# general_Interface.net
KiCad netlist of a schematic drawn in Altium Designer
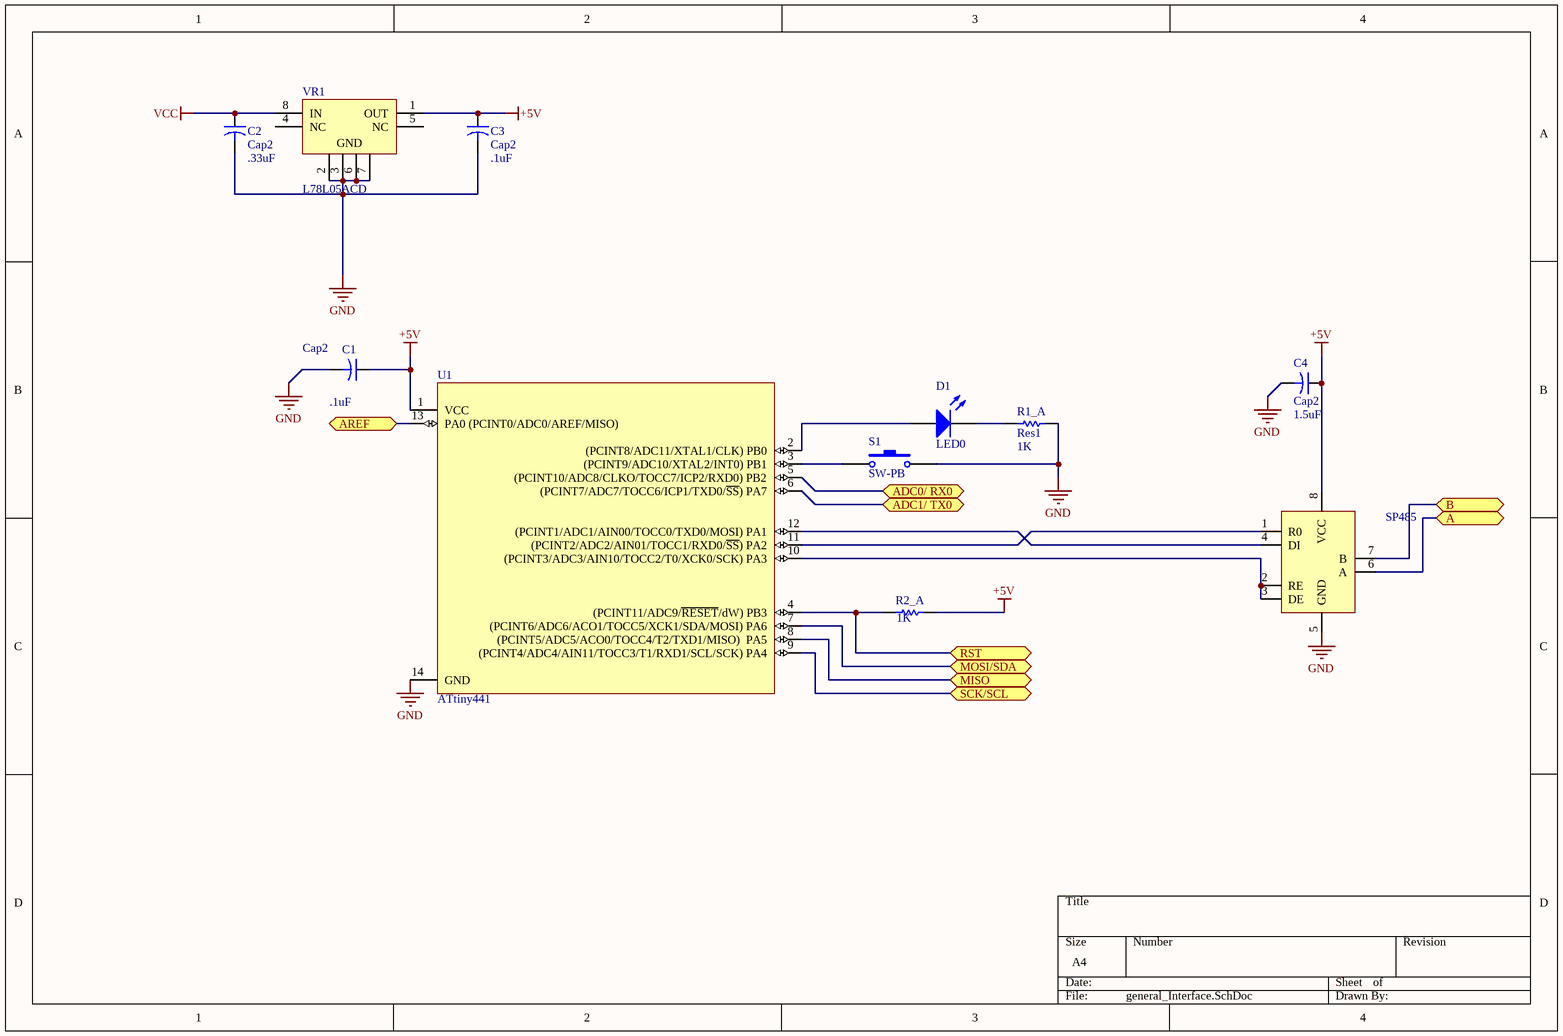
[diagram p0: general_Interface.SchDoc]

(export (version "E")
  (design (tool "Eeschema 10.0.6"))
  (components
    (comp (ref "C1")
      (value "Cap2")
      (footprint "6-0805_N")
      (description "Capacitor")
      (fields (field (name "ALTIUM_VALUE") ".1uF") (field (name "PUBLISHER") "Altium Limited"))
      (libsource (lib "Miscellaneous Devices") (part "Cap2"))
    )
    (comp (ref "C2")
      (value "Cap2")
      (footprint "6-0805_N")
      (description "Capacitor")
      (fields (field (name "ALTIUM_VALUE") ".33uF") (field (name "PUBLISHER") "Altium Limited"))
      (libsource (lib "Miscellaneous Devices") (part "Cap2"))
    )
    (comp (ref "C3")
      (value "Cap2")
      (footprint "6-0805_N")
      (description "Capacitor")
      (fields (field (name "ALTIUM_VALUE") ".1uF") (field (name "PUBLISHER") "Altium Limited"))
      (libsource (lib "Miscellaneous Devices") (part "Cap2"))
    )
    (comp (ref "C4")
      (value "Cap2")
      (footprint "6-0805_N")
      (description "Capacitor")
      (fields (field (name "ALTIUM_VALUE") "1.5uF") (field (name "PUBLISHER") "Altium Limited"))
      (libsource (lib "Miscellaneous Devices") (part "Cap2"))
    )
    (comp (ref "D1")
      (value "LED0")
      (footprint "1608[0603]")
      (description "Typical INFRARED GaAs LED")
      (fields (field (name "PUBLISHER") "Altium Limited"))
      (libsource (lib "Miscellaneous Devices") (part "LED0"))
    )
    (comp (ref "R1_A")
      (value "Res1")
      (footprint "6-0805_N")
      (description "Resistor")
      (fields (field (name "ALTIUM_VALUE") "1K") (field (name "PUBLISHER") "Altium Limited"))
      (libsource (lib "Miscellaneous Devices") (part "Res1"))
    )
    (comp (ref "R2_A")
      (value "1K")
      (footprint "J1-0603")
      (description "Resistor")
      (fields (field (name "Comment") "Res1") (field (name "PUBLISHER") "Altium Limited"))
      (libsource (lib "Miscellaneous Devices") (part "Res1"))
    )
    (comp (ref "S1")
      (value "SW-PB")
      (footprint "ADTSM3")
      (description "Switch")
      (fields (field (name "PUBLISHER") "Altium Limited"))
      (libsource (lib "Miscellaneous Devices") (part "SW-PB"))
    )
    (comp (ref "SP485") (value "SP485") (footprint "8S1_M") (libsource (lib "MABSS") (part "SP485")))
    (comp (ref "U1") (value "ATtiny441") (footprint "6ST1_L") (libsource (lib "MABSS") (part "ATtiny441")))
    (comp (ref "VR1")
      (value "L78L05ACD")
      (footprint "8S1_N")
      (description "Positive Voltage Regulator")
      (fields (field (name "PUBLISHER") "Altium Limited"))
      (libsource (lib "ST Power Mgt Voltage Regulator") (part "L78L05ACD"))
    )
  )
  (nets
    (net (code "1") (name "+5V") (class "Default")
      (node (ref "C1") (pin "1") (pinfunction "1_1") (pintype "passive"))
      (node (ref "C3") (pin "1") (pinfunction "1_1") (pintype "passive"))
      (node (ref "C4") (pin "1") (pinfunction "1_1") (pintype "passive"))
      (node (ref "R2_A") (pin "2") (pinfunction "2_2") (pintype "passive"))
      (node (ref "SP485") (pin "8") (pinfunction "VCC_8") (pintype "passive"))
      (node (ref "U1") (pin "1") (pinfunction "VCC_1") (pintype "power_in"))
      (node (ref "VR1") (pin "1") (pinfunction "OUT_1") (pintype "power_in"))
    )
    (net (code "2") (name "/A") (class "Default")
      (node (ref "SP485") (pin "6") (pinfunction "A_6") (pintype "passive"))
    )
    (net (code "3") (name "/ADC0{slash} RX0") (class "Default")
      (node (ref "U1") (pin "5") (pinfunction "(PCINT10/ADC8/CLKO/TOCC7/ICP2/RXD0)_PB2_5") (pintype "bidirectional"))
    )
    (net (code "4") (name "/ADC1{slash} TX0") (class "Default")
      (node (ref "U1") (pin "6") (pinfunction "(PCINT7/ADC7/TOCC6/ICP1/TXD0/~{SS})_PA7_6") (pintype "bidirectional"))
    )
    (net (code "5") (name "/AREF") (class "Default")
      (node (ref "U1") (pin "13") (pinfunction "PA0_(PCINT0/ADC0/AREF/MISO)_13") (pintype "bidirectional"))
    )
    (net (code "6") (name "/B") (class "Default")
      (node (ref "SP485") (pin "7") (pinfunction "B_7") (pintype "passive"))
    )
    (net (code "7") (name "/MISO") (class "Default")
      (node (ref "U1") (pin "8") (pinfunction "(PCINT5/ADC5/ACO0/TOCC4/T2/TXD1/MISO)__PA5_8") (pintype "bidirectional"))
    )
    (net (code "8") (name "/MOSI{slash}SDA") (class "Default")
      (node (ref "U1") (pin "7") (pinfunction "(PCINT6/ADC6/ACO1/TOCC5/XCK1/SDA/MOSI)_PA6_7") (pintype "bidirectional"))
    )
    (net (code "9") (name "/RST") (class "Default")
      (node (ref "R2_A") (pin "1") (pinfunction "1_1") (pintype "passive"))
      (node (ref "U1") (pin "4") (pinfunction "(PCINT11/ADC9/~{RESET}/dW)_PB3_4") (pintype "bidirectional"))
    )
    (net (code "10") (name "/SCK{slash}SCL") (class "Default")
      (node (ref "U1") (pin "9") (pinfunction "(PCINT4/ADC4/AIN11/TOCC3/T1/RXD1/SCL/SCK)_PA4_9") (pintype "bidirectional"))
    )
    (net (code "11") (name "GND") (class "Default")
      (node (ref "C1") (pin "2") (pinfunction "2_2") (pintype "passive"))
      (node (ref "C2") (pin "2") (pinfunction "2_2") (pintype "passive"))
      (node (ref "C3") (pin "2") (pinfunction "2_2") (pintype "passive"))
      (node (ref "C4") (pin "2") (pinfunction "2_2") (pintype "passive"))
      (node (ref "R1_A") (pin "2") (pinfunction "2_2") (pintype "passive"))
      (node (ref "S1") (pin "2") (pinfunction "2_2") (pintype "passive"))
      (node (ref "SP485") (pin "5") (pinfunction "GND_5") (pintype "passive"))
      (node (ref "U1") (pin "14") (pinfunction "GND_14") (pintype "power_in"))
      (node (ref "VR1") (pin "2") (pinfunction "GND_2") (pintype "power_in"))
      (node (ref "VR1") (pin "3") (pinfunction "GND_3") (pintype "power_in"))
      (node (ref "VR1") (pin "6") (pinfunction "GND_6") (pintype "power_in"))
      (node (ref "VR1") (pin "7") (pinfunction "GND_7") (pintype "power_in"))
    )
    (net (code "12") (name "Net-(D1-A)") (class "Default")
      (node (ref "D1") (pin "1") (pinfunction "A_1") (pintype "passive"))
      (node (ref "U1") (pin "2") (pinfunction "(PCINT8/ADC11/XTAL1/CLK)_PB0_2") (pintype "bidirectional"))
    )
    (net (code "13") (name "Net-(D1-K)") (class "Default")
      (node (ref "D1") (pin "2") (pinfunction "K_2") (pintype "passive"))
      (node (ref "R1_A") (pin "1") (pinfunction "1_1") (pintype "passive"))
    )
    (net (code "14") (name "Net-(SP485-DE)") (class "Default")
      (node (ref "SP485") (pin "2") (pinfunction "RE_2") (pintype "passive"))
      (node (ref "SP485") (pin "3") (pinfunction "DE_3") (pintype "passive"))
      (node (ref "U1") (pin "10") (pinfunction "(PCINT3/ADC3/AIN10/TOCC2/T0/XCK0/SCK)_PA3_10") (pintype "bidirectional"))
    )
    (net (code "15") (name "Net-(SP485-DI)") (class "Default")
      (node (ref "SP485") (pin "4") (pinfunction "DI_4") (pintype "passive"))
      (node (ref "U1") (pin "12") (pinfunction "(PCINT1/ADC1/AIN00/TOCC0/TXD0/MOSI)_PA1_12") (pintype "bidirectional"))
    )
    (net (code "16") (name "Net-(SP485-R0)") (class "Default")
      (node (ref "SP485") (pin "1") (pinfunction "R0_1") (pintype "passive"))
      (node (ref "U1") (pin "11") (pinfunction "(PCINT2/ADC2/AIN01/TOCC1/RXD0/~{SS})_PA2_11") (pintype "bidirectional"))
    )
    (net (code "17") (name "Net-(U1-(PCINT9{slash}ADC10{slash}XTAL2{slash}INT0)_PB1)") (class "Default")
      (node (ref "S1") (pin "1") (pinfunction "1_1") (pintype "passive"))
      (node (ref "U1") (pin "3") (pinfunction "(PCINT9/ADC10/XTAL2/INT0)_PB1_3") (pintype "bidirectional"))
    )
    (net (code "18") (name "VCC") (class "Default")
      (node (ref "C2") (pin "1") (pinfunction "1_1") (pintype "passive"))
      (node (ref "VR1") (pin "8") (pinfunction "IN_8") (pintype "power_in"))
    )
    (net (code "19") (name "unconnected-(VR1-NC-Pad4)") (class "Default")
      (node (ref "VR1") (pin "4") (pinfunction "NC_4") (pintype "passive"))
    )
    (net (code "20") (name "unconnected-(VR1-NC-Pad5)") (class "Default")
      (node (ref "VR1") (pin "5") (pinfunction "NC_5") (pintype "passive"))
    )
  )
)
